# STM32_MPU_IOs.net
KiCad netlist of a schematic drawn in Altium Designer
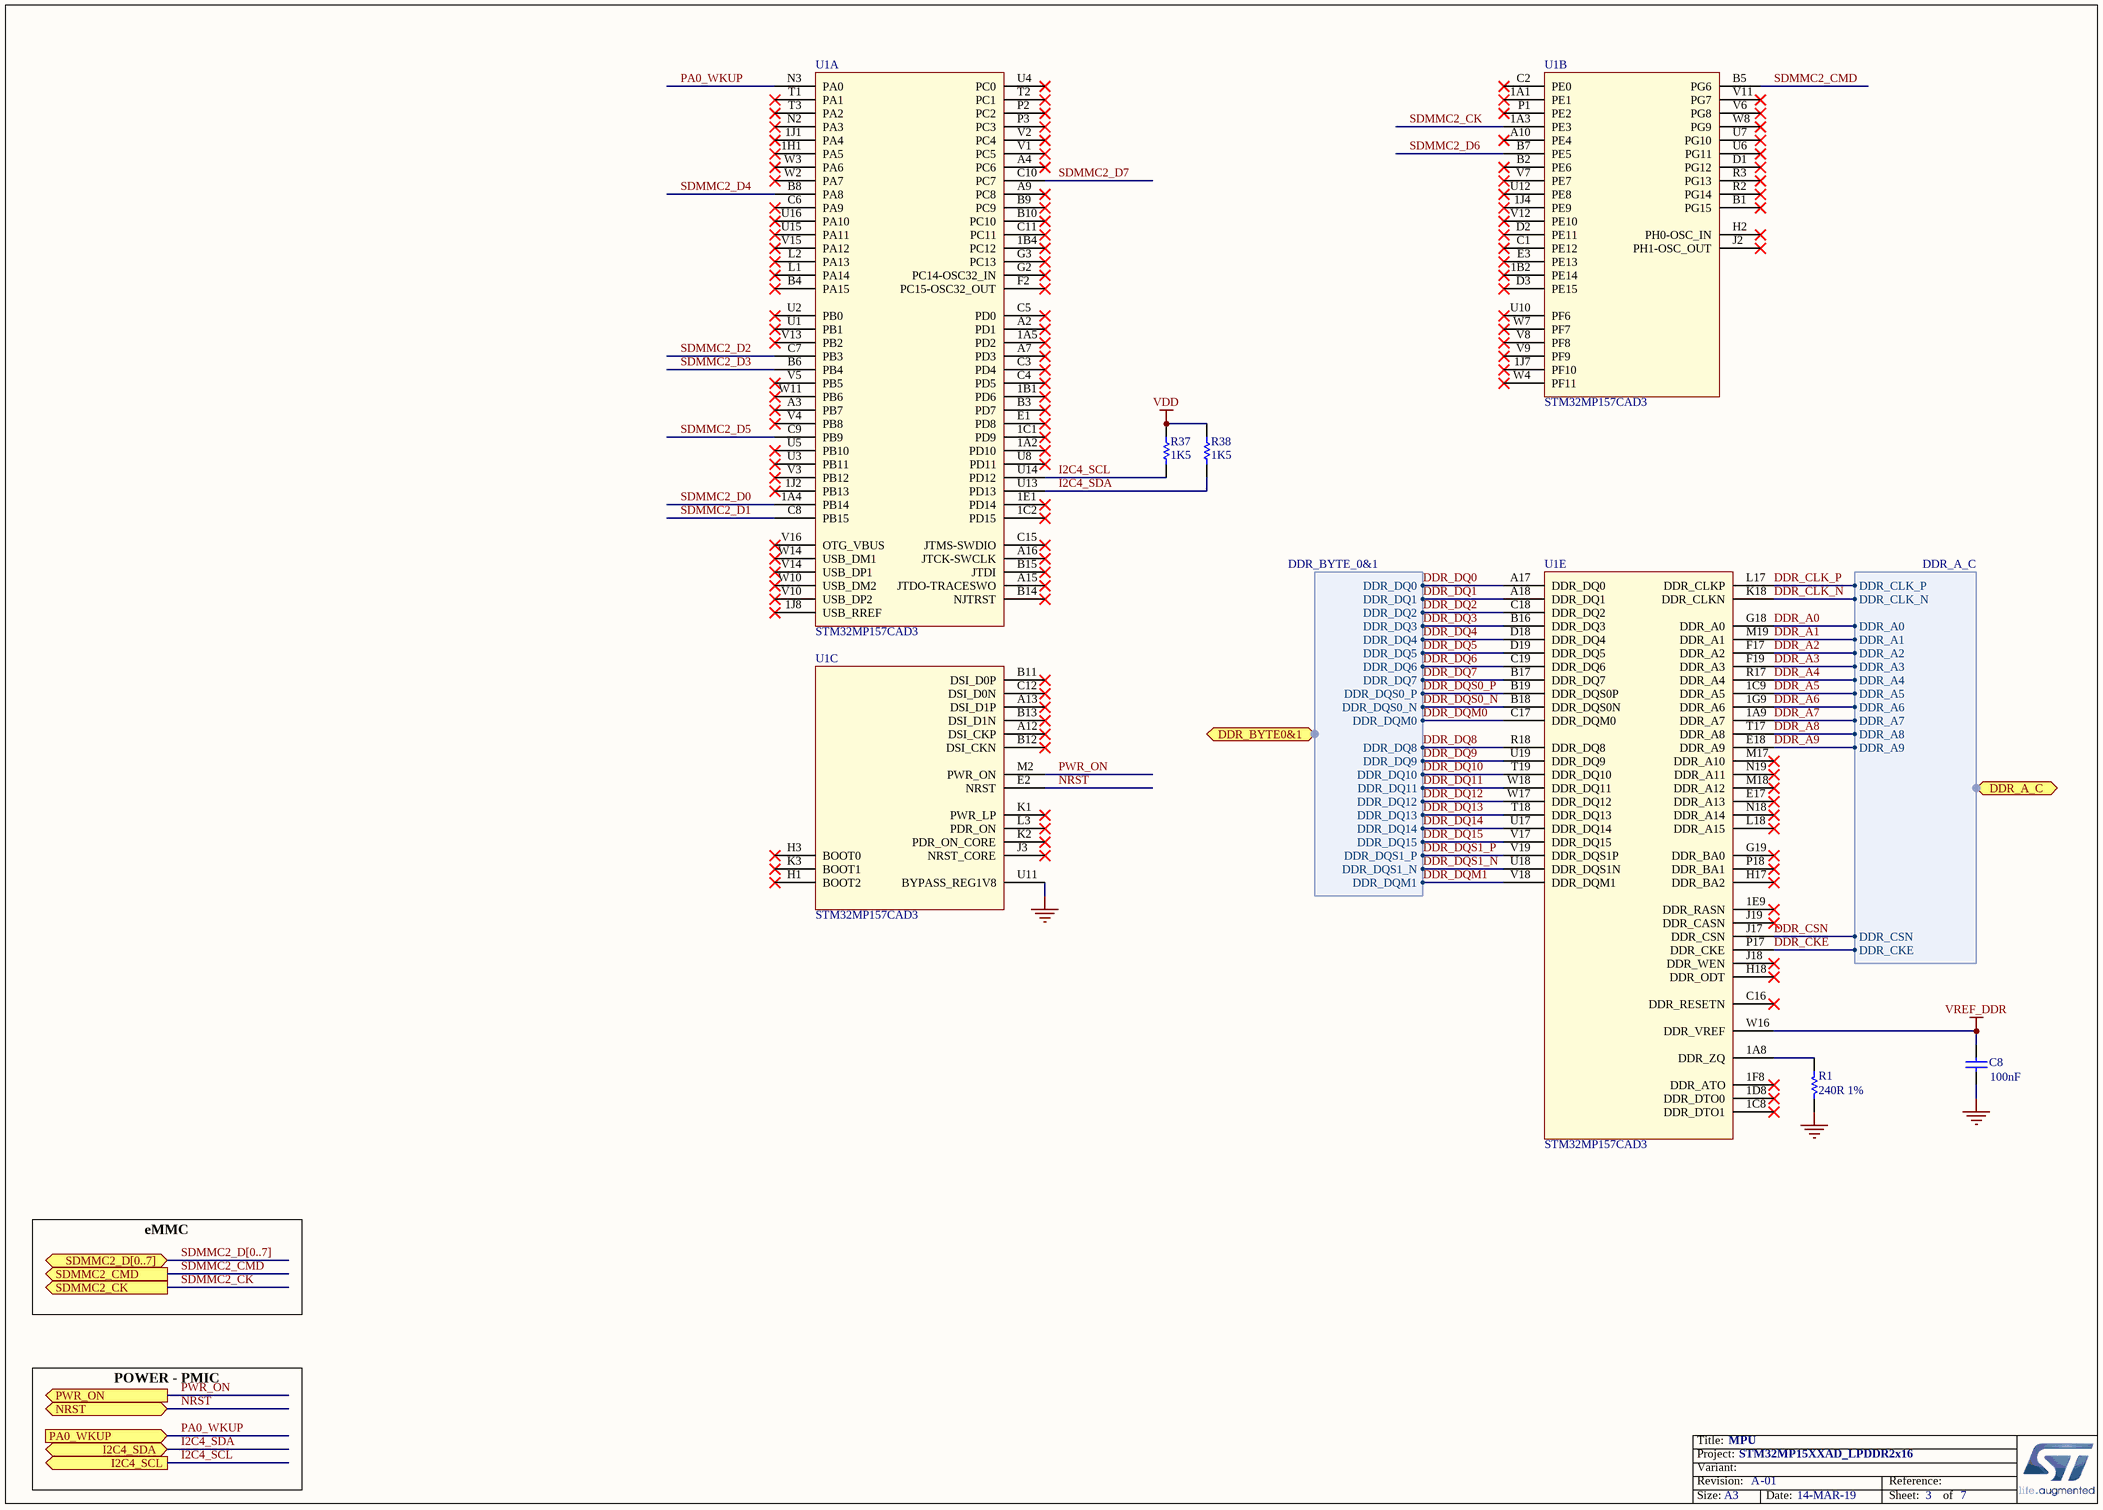
[diagram p0: STM32_MPU_IOs.SchDoc]

(export (version "E")
  (design (tool "Eeschema 10.0.6"))
  (components
    (comp (ref "C8")
      (value "100nF")
      (footprint "C0402")
      (description "Capacitor, MLCC, 100nF, 16V, X7R, 10%, 0402, T=0.5mm")
      (fields
        (field (name "INTERNAL_PART_NUMBER") "MCD-00006")
        (field (name "MANUFACTURER_PART_NUMBER") "CC0402KRX7R7BB104")
        (field (name "PROVIDED_BY") "SUBCO")
      )
      (libsource (lib "MCD_PARTS_database") (part "Capacitor"))
    )
    (comp (ref "R1")
      (value "240R 1%")
      (footprint "R0402")
      (description "Resistor,240R,0402,1%,1/16W")
      (fields
        (field (name "INTERNAL_PART_NUMBER") "MCD-00120")
        (field (name "MANUFACTURER_PART_NUMBER") "RC0402FR-07240RL")
        (field (name "PROVIDED_BY") "SUBCO")
      )
      (libsource (lib "MCD_PARTS_database") (part "Resistor"))
    )
    (comp (ref "R37")
      (value "1K5")
      (footprint "R0402")
      (description "Resistor,1K5,0402,1%,1/16W")
      (fields
        (field (name "INTERNAL_PART_NUMBER") "MCD-00068")
        (field (name "MANUFACTURER_PART_NUMBER") "RC0402FR-071K5L")
        (field (name "PROVIDED_BY") "SUBCO")
      )
      (libsource (lib "MCD_PARTS_database") (part "Resistor"))
    )
    (comp (ref "R38")
      (value "1K5")
      (footprint "R0402")
      (description "Resistor,1K5,0402,1%,1/16W")
      (fields
        (field (name "INTERNAL_PART_NUMBER") "MCD-00068")
        (field (name "MANUFACTURER_PART_NUMBER") "RC0402FR-071K5L")
        (field (name "PROVIDED_BY") "SUBCO")
      )
      (libsource (lib "MCD_PARTS_database") (part "Resistor"))
    )
    (comp (ref "U1")
      (value "STM32MP157CAD3")
      (footprint "ICC_TFBGA257_10X10_STM32MP157CAD3_P050-065")
      (description "MPU TFBGA10x10 secure boot+crypto")
      (fields
        (field (name "INTERNAL_PART_NUMBER") "MCD-01144")
        (field (name "MANUFACTURER") "STMICROELECTRONICS")
        (field (name "PROVIDED_BY") "SUBCO with ST control")
      )
      (libsource (lib "MCD_PARTS_database") (part "STM32MP157CAD3"))
    )
  )
  (nets
    (net (code "3") (name "/DDR_A0") (class "Default")
      (node (ref "U1") (pin "G18") (pinfunction "DDR_A0_G18") (pintype "passive"))
    )
    (net (code "4") (name "/DDR_A1") (class "Default")
      (node (ref "U1") (pin "M19") (pinfunction "DDR_A1_M19") (pintype "passive"))
    )
    (net (code "5") (name "/DDR_A2") (class "Default")
      (node (ref "U1") (pin "F17") (pinfunction "DDR_A2_F17") (pintype "passive"))
    )
    (net (code "6") (name "/DDR_A3") (class "Default")
      (node (ref "U1") (pin "F19") (pinfunction "DDR_A3_F19") (pintype "passive"))
    )
    (net (code "7") (name "/DDR_A4") (class "Default")
      (node (ref "U1") (pin "R17") (pinfunction "DDR_A4_R17") (pintype "passive"))
    )
    (net (code "8") (name "/DDR_A5") (class "Default")
      (node (ref "U1") (pin "1C9") (pinfunction "DDR_A5_1C9") (pintype "passive"))
    )
    (net (code "9") (name "/DDR_A6") (class "Default")
      (node (ref "U1") (pin "1G9") (pinfunction "DDR_A6_1G9") (pintype "passive"))
    )
    (net (code "10") (name "/DDR_A7") (class "Default")
      (node (ref "U1") (pin "1A9") (pinfunction "DDR_A7_1A9") (pintype "passive"))
    )
    (net (code "11") (name "/DDR_A8") (class "Default")
      (node (ref "U1") (pin "T17") (pinfunction "DDR_A8_T17") (pintype "passive"))
    )
    (net (code "12") (name "/DDR_A9") (class "Default")
      (node (ref "U1") (pin "E18") (pinfunction "DDR_A9_E18") (pintype "passive"))
    )
    (net (code "13") (name "/DDR_CKE") (class "Default")
      (node (ref "U1") (pin "P17") (pinfunction "DDR_CKE_P17") (pintype "passive"))
    )
    (net (code "14") (name "/DDR_CLK_N") (class "Default")
      (node (ref "U1") (pin "K18") (pinfunction "DDR_CLKN_K18") (pintype "passive"))
    )
    (net (code "15") (name "/DDR_CLK_P") (class "Default")
      (node (ref "U1") (pin "L17") (pinfunction "DDR_CLKP_L17") (pintype "passive"))
    )
    (net (code "16") (name "/DDR_CSN") (class "Default")
      (node (ref "U1") (pin "J17") (pinfunction "DDR_CSN_J17") (pintype "passive"))
    )
    (net (code "17") (name "/DDR_DQ0") (class "Default")
      (node (ref "U1") (pin "A17") (pinfunction "DDR_DQ0_A17") (pintype "passive"))
    )
    (net (code "18") (name "/DDR_DQ1") (class "Default")
      (node (ref "U1") (pin "A18") (pinfunction "DDR_DQ1_A18") (pintype "passive"))
    )
    (net (code "19") (name "/DDR_DQ2") (class "Default")
      (node (ref "U1") (pin "C18") (pinfunction "DDR_DQ2_C18") (pintype "passive"))
    )
    (net (code "20") (name "/DDR_DQ3") (class "Default")
      (node (ref "U1") (pin "B16") (pinfunction "DDR_DQ3_B16") (pintype "passive"))
    )
    (net (code "21") (name "/DDR_DQ4") (class "Default")
      (node (ref "U1") (pin "D18") (pinfunction "DDR_DQ4_D18") (pintype "passive"))
    )
    (net (code "22") (name "/DDR_DQ5") (class "Default")
      (node (ref "U1") (pin "D19") (pinfunction "DDR_DQ5_D19") (pintype "passive"))
    )
    (net (code "23") (name "/DDR_DQ6") (class "Default")
      (node (ref "U1") (pin "C19") (pinfunction "DDR_DQ6_C19") (pintype "passive"))
    )
    (net (code "24") (name "/DDR_DQ7") (class "Default")
      (node (ref "U1") (pin "B17") (pinfunction "DDR_DQ7_B17") (pintype "passive"))
    )
    (net (code "25") (name "/DDR_DQ8") (class "Default")
      (node (ref "U1") (pin "R18") (pinfunction "DDR_DQ8_R18") (pintype "passive"))
    )
    (net (code "26") (name "/DDR_DQ9") (class "Default")
      (node (ref "U1") (pin "U19") (pinfunction "DDR_DQ9_U19") (pintype "passive"))
    )
    (net (code "27") (name "/DDR_DQ10") (class "Default")
      (node (ref "U1") (pin "T19") (pinfunction "DDR_DQ10_T19") (pintype "passive"))
    )
    (net (code "28") (name "/DDR_DQ11") (class "Default")
      (node (ref "U1") (pin "W18") (pinfunction "DDR_DQ11_W18") (pintype "passive"))
    )
    (net (code "29") (name "/DDR_DQ12") (class "Default")
      (node (ref "U1") (pin "W17") (pinfunction "DDR_DQ12_W17") (pintype "passive"))
    )
    (net (code "30") (name "/DDR_DQ13") (class "Default")
      (node (ref "U1") (pin "T18") (pinfunction "DDR_DQ13_T18") (pintype "passive"))
    )
    (net (code "31") (name "/DDR_DQ14") (class "Default")
      (node (ref "U1") (pin "U17") (pinfunction "DDR_DQ14_U17") (pintype "passive"))
    )
    (net (code "32") (name "/DDR_DQ15") (class "Default")
      (node (ref "U1") (pin "V17") (pinfunction "DDR_DQ15_V17") (pintype "passive"))
    )
    (net (code "33") (name "/DDR_DQM0") (class "Default")
      (node (ref "U1") (pin "C17") (pinfunction "DDR_DQM0_C17") (pintype "passive"))
    )
    (net (code "34") (name "/DDR_DQM1") (class "Default")
      (node (ref "U1") (pin "V18") (pinfunction "DDR_DQM1_V18") (pintype "passive"))
    )
    (net (code "35") (name "/DDR_DQS0_N") (class "Default")
      (node (ref "U1") (pin "B18") (pinfunction "DDR_DQS0N_B18") (pintype "passive"))
    )
    (net (code "36") (name "/DDR_DQS0_P") (class "Default")
      (node (ref "U1") (pin "B19") (pinfunction "DDR_DQS0P_B19") (pintype "passive"))
    )
    (net (code "37") (name "/DDR_DQS1_N") (class "Default")
      (node (ref "U1") (pin "U18") (pinfunction "DDR_DQS1N_U18") (pintype "passive"))
    )
    (net (code "38") (name "/DDR_DQS1_P") (class "Default")
      (node (ref "U1") (pin "V19") (pinfunction "DDR_DQS1P_V19") (pintype "passive"))
    )
    (net (code "39") (name "/I2C4_SCL") (class "Default")
      (node (ref "R37") (pin "2") (pinfunction "2_2") (pintype "passive"))
      (node (ref "U1") (pin "U14") (pinfunction "PD12_U14") (pintype "passive"))
    )
    (net (code "40") (name "/I2C4_SDA") (class "Default")
      (node (ref "R38") (pin "2") (pinfunction "2_2") (pintype "passive"))
      (node (ref "U1") (pin "U13") (pinfunction "PD13_U13") (pintype "passive"))
    )
    (net (code "41") (name "/NRST") (class "Default")
      (node (ref "U1") (pin "E2") (pinfunction "NRST_E2") (pintype "passive"))
    )
    (net (code "42") (name "/PA0_WKUP") (class "Default")
      (node (ref "U1") (pin "N3") (pinfunction "PA0_N3") (pintype "passive"))
    )
    (net (code "43") (name "/PWR_ON") (class "Default")
      (node (ref "U1") (pin "M2") (pinfunction "PWR_ON_M2") (pintype "passive"))
    )
    (net (code "44") (name "/SDMMC2_CK") (class "Default")
      (node (ref "U1") (pin "1A3") (pinfunction "PE3_1A3") (pintype "passive"))
    )
    (net (code "45") (name "/SDMMC2_CMD") (class "Default")
      (node (ref "U1") (pin "B5") (pinfunction "PG6_B5") (pintype "passive"))
    )
    (net (code "46") (name "/SDMMC2_D0") (class "Default")
      (node (ref "U1") (pin "1A4") (pinfunction "PB14_1A4") (pintype "passive"))
    )
    (net (code "47") (name "/SDMMC2_D1") (class "Default")
      (node (ref "U1") (pin "C8") (pinfunction "PB15_C8") (pintype "passive"))
    )
    (net (code "48") (name "/SDMMC2_D2") (class "Default")
      (node (ref "U1") (pin "C7") (pinfunction "PB3_C7") (pintype "passive"))
    )
    (net (code "49") (name "/SDMMC2_D3") (class "Default")
      (node (ref "U1") (pin "B6") (pinfunction "PB4_B6") (pintype "passive"))
    )
    (net (code "50") (name "/SDMMC2_D4") (class "Default")
      (node (ref "U1") (pin "B8") (pinfunction "PA8_B8") (pintype "passive"))
    )
    (net (code "51") (name "/SDMMC2_D5") (class "Default")
      (node (ref "U1") (pin "C9") (pinfunction "PB9_C9") (pintype "passive"))
    )
    (net (code "52") (name "/SDMMC2_D6") (class "Default")
      (node (ref "U1") (pin "B7") (pinfunction "PE5_B7") (pintype "passive"))
    )
    (net (code "53") (name "/SDMMC2_D7") (class "Default")
      (node (ref "U1") (pin "C10") (pinfunction "PC7_C10") (pintype "passive"))
    )
    (net (code "57") (name "GND") (class "Default")
      (node (ref "C8") (pin "1") (pinfunction "1_1") (pintype "passive"))
      (node (ref "R1") (pin "2") (pinfunction "2_2") (pintype "passive"))
      (node (ref "U1") (pin "U11") (pinfunction "BYPASS_REG1V8_U11") (pintype "passive"))
    )
    (net (code "58") (name "Net-(U1E-DDR_ZQ)") (class "Default")
      (node (ref "R1") (pin "1") (pinfunction "1_1") (pintype "passive"))
      (node (ref "U1") (pin "1A8") (pinfunction "DDR_ZQ_1A8") (pintype "passive"))
    )
    (net (code "59") (name "VDD") (class "Default")
      (node (ref "R37") (pin "1") (pinfunction "1_1") (pintype "passive"))
      (node (ref "R38") (pin "1") (pinfunction "1_1") (pintype "passive"))
    )
    (net (code "60") (name "VREF_DDR") (class "Default")
      (node (ref "C8") (pin "2") (pinfunction "2_2") (pintype "passive"))
      (node (ref "U1") (pin "W16") (pinfunction "DDR_VREF_W16") (pintype "passive"))
    )
    (net (code "61") (name "unconnected-(U1A-JTCK-SWCLK-PadA16)") (class "Default")
      (node (ref "U1") (pin "A16") (pinfunction "JTCK-SWCLK_A16") (pintype "passive+no_connect"))
    )
    (net (code "62") (name "unconnected-(U1A-JTDI-PadB15)") (class "Default")
      (node (ref "U1") (pin "B15") (pinfunction "JTDI_B15") (pintype "passive+no_connect"))
    )
    (net (code "63") (name "unconnected-(U1A-JTDO-TRACESWO-PadA15)") (class "Default")
      (node (ref "U1") (pin "A15") (pinfunction "JTDO-TRACESWO_A15") (pintype "passive+no_connect"))
    )
    (net (code "64") (name "unconnected-(U1A-JTMS-SWDIO-PadC15)") (class "Default")
      (node (ref "U1") (pin "C15") (pinfunction "JTMS-SWDIO_C15") (pintype "passive+no_connect"))
    )
    (net (code "65") (name "unconnected-(U1A-NJTRST-PadB14)") (class "Default")
      (node (ref "U1") (pin "B14") (pinfunction "NJTRST_B14") (pintype "passive+no_connect"))
    )
    (net (code "66") (name "unconnected-(U1A-OTG_VBUS-PadV16)") (class "Default")
      (node (ref "U1") (pin "V16") (pinfunction "OTG_VBUS_V16") (pintype "passive+no_connect"))
    )
    (net (code "67") (name "unconnected-(U1A-PA1-PadT1)") (class "Default")
      (node (ref "U1") (pin "T1") (pinfunction "PA1_T1") (pintype "passive+no_connect"))
    )
    (net (code "68") (name "unconnected-(U1A-PA2-PadT3)") (class "Default")
      (node (ref "U1") (pin "T3") (pinfunction "PA2_T3") (pintype "passive+no_connect"))
    )
    (net (code "69") (name "unconnected-(U1A-PA3-PadN2)") (class "Default")
      (node (ref "U1") (pin "N2") (pinfunction "PA3_N2") (pintype "passive+no_connect"))
    )
    (net (code "70") (name "unconnected-(U1A-PA4-Pad1J1)") (class "Default")
      (node (ref "U1") (pin "1J1") (pinfunction "PA4_1J1") (pintype "passive+no_connect"))
    )
    (net (code "71") (name "unconnected-(U1A-PA5-Pad1H1)") (class "Default")
      (node (ref "U1") (pin "1H1") (pinfunction "PA5_1H1") (pintype "passive+no_connect"))
    )
    (net (code "72") (name "unconnected-(U1A-PA6-PadW3)") (class "Default")
      (node (ref "U1") (pin "W3") (pinfunction "PA6_W3") (pintype "passive+no_connect"))
    )
    (net (code "73") (name "unconnected-(U1A-PA7-PadW2)") (class "Default")
      (node (ref "U1") (pin "W2") (pinfunction "PA7_W2") (pintype "passive+no_connect"))
    )
    (net (code "74") (name "unconnected-(U1A-PA9-PadC6)") (class "Default")
      (node (ref "U1") (pin "C6") (pinfunction "PA9_C6") (pintype "passive+no_connect"))
    )
    (net (code "75") (name "unconnected-(U1A-PA10-PadU16)") (class "Default")
      (node (ref "U1") (pin "U16") (pinfunction "PA10_U16") (pintype "passive+no_connect"))
    )
    (net (code "76") (name "unconnected-(U1A-PA11-PadU15)") (class "Default")
      (node (ref "U1") (pin "U15") (pinfunction "PA11_U15") (pintype "passive+no_connect"))
    )
    (net (code "77") (name "unconnected-(U1A-PA12-PadV15)") (class "Default")
      (node (ref "U1") (pin "V15") (pinfunction "PA12_V15") (pintype "passive+no_connect"))
    )
    (net (code "78") (name "unconnected-(U1A-PA13-PadL2)") (class "Default")
      (node (ref "U1") (pin "L2") (pinfunction "PA13_L2") (pintype "passive+no_connect"))
    )
    (net (code "79") (name "unconnected-(U1A-PA14-PadL1)") (class "Default")
      (node (ref "U1") (pin "L1") (pinfunction "PA14_L1") (pintype "passive+no_connect"))
    )
    (net (code "80") (name "unconnected-(U1A-PA15-PadB4)") (class "Default")
      (node (ref "U1") (pin "B4") (pinfunction "PA15_B4") (pintype "passive+no_connect"))
    )
    (net (code "81") (name "unconnected-(U1A-PB0-PadU2)") (class "Default")
      (node (ref "U1") (pin "U2") (pinfunction "PB0_U2") (pintype "passive+no_connect"))
    )
    (net (code "82") (name "unconnected-(U1A-PB1-PadU1)") (class "Default")
      (node (ref "U1") (pin "U1") (pinfunction "PB1_U1") (pintype "passive+no_connect"))
    )
    (net (code "83") (name "unconnected-(U1A-PB2-PadV13)") (class "Default")
      (node (ref "U1") (pin "V13") (pinfunction "PB2_V13") (pintype "passive+no_connect"))
    )
    (net (code "84") (name "unconnected-(U1A-PB5-PadV5)") (class "Default")
      (node (ref "U1") (pin "V5") (pinfunction "PB5_V5") (pintype "passive+no_connect"))
    )
    (net (code "85") (name "unconnected-(U1A-PB6-PadW11)") (class "Default")
      (node (ref "U1") (pin "W11") (pinfunction "PB6_W11") (pintype "passive+no_connect"))
    )
    (net (code "86") (name "unconnected-(U1A-PB7-PadA3)") (class "Default")
      (node (ref "U1") (pin "A3") (pinfunction "PB7_A3") (pintype "passive+no_connect"))
    )
    (net (code "87") (name "unconnected-(U1A-PB8-PadV4)") (class "Default")
      (node (ref "U1") (pin "V4") (pinfunction "PB8_V4") (pintype "passive+no_connect"))
    )
    (net (code "88") (name "unconnected-(U1A-PB10-PadU5)") (class "Default")
      (node (ref "U1") (pin "U5") (pinfunction "PB10_U5") (pintype "passive+no_connect"))
    )
    (net (code "89") (name "unconnected-(U1A-PB11-PadU3)") (class "Default")
      (node (ref "U1") (pin "U3") (pinfunction "PB11_U3") (pintype "passive+no_connect"))
    )
    (net (code "90") (name "unconnected-(U1A-PB12-PadV3)") (class "Default")
      (node (ref "U1") (pin "V3") (pinfunction "PB12_V3") (pintype "passive+no_connect"))
    )
    (net (code "91") (name "unconnected-(U1A-PB13-Pad1J2)") (class "Default")
      (node (ref "U1") (pin "1J2") (pinfunction "PB13_1J2") (pintype "passive+no_connect"))
    )
    (net (code "92") (name "unconnected-(U1A-PC0-PadU4)") (class "Default")
      (node (ref "U1") (pin "U4") (pinfunction "PC0_U4") (pintype "passive+no_connect"))
    )
    (net (code "93") (name "unconnected-(U1A-PC1-PadT2)") (class "Default")
      (node (ref "U1") (pin "T2") (pinfunction "PC1_T2") (pintype "passive+no_connect"))
    )
    (net (code "94") (name "unconnected-(U1A-PC2-PadP2)") (class "Default")
      (node (ref "U1") (pin "P2") (pinfunction "PC2_P2") (pintype "passive+no_connect"))
    )
    (net (code "95") (name "unconnected-(U1A-PC3-PadP3)") (class "Default")
      (node (ref "U1") (pin "P3") (pinfunction "PC3_P3") (pintype "passive+no_connect"))
    )
    (net (code "96") (name "unconnected-(U1A-PC4-PadV2)") (class "Default")
      (node (ref "U1") (pin "V2") (pinfunction "PC4_V2") (pintype "passive+no_connect"))
    )
    (net (code "97") (name "unconnected-(U1A-PC5-PadV1)") (class "Default")
      (node (ref "U1") (pin "V1") (pinfunction "PC5_V1") (pintype "passive+no_connect"))
    )
    (net (code "98") (name "unconnected-(U1A-PC6-PadA4)") (class "Default")
      (node (ref "U1") (pin "A4") (pinfunction "PC6_A4") (pintype "passive+no_connect"))
    )
    (net (code "99") (name "unconnected-(U1A-PC8-PadA9)") (class "Default")
      (node (ref "U1") (pin "A9") (pinfunction "PC8_A9") (pintype "passive+no_connect"))
    )
    (net (code "100") (name "unconnected-(U1A-PC9-PadB9)") (class "Default")
      (node (ref "U1") (pin "B9") (pinfunction "PC9_B9") (pintype "passive+no_connect"))
    )
    (net (code "101") (name "unconnected-(U1A-PC10-PadB10)") (class "Default")
      (node (ref "U1") (pin "B10") (pinfunction "PC10_B10") (pintype "passive+no_connect"))
    )
    (net (code "102") (name "unconnected-(U1A-PC11-PadC11)") (class "Default")
      (node (ref "U1") (pin "C11") (pinfunction "PC11_C11") (pintype "passive+no_connect"))
    )
    (net (code "103") (name "unconnected-(U1A-PC12-Pad1B4)") (class "Default")
      (node (ref "U1") (pin "1B4") (pinfunction "PC12_1B4") (pintype "passive+no_connect"))
    )
    (net (code "104") (name "unconnected-(U1A-PC13-PadG3)") (class "Default")
      (node (ref "U1") (pin "G3") (pinfunction "PC13_G3") (pintype "passive+no_connect"))
    )
    (net (code "105") (name "unconnected-(U1A-PC14-OSC32_IN-PadG2)") (class "Default")
      (node (ref "U1") (pin "G2") (pinfunction "PC14-OSC32_IN_G2") (pintype "passive+no_connect"))
    )
    (net (code "106") (name "unconnected-(U1A-PC15-OSC32_OUT-PadF2)") (class "Default")
      (node (ref "U1") (pin "F2") (pinfunction "PC15-OSC32_OUT_F2") (pintype "passive+no_connect"))
    )
    (net (code "107") (name "unconnected-(U1A-PD0-PadC5)") (class "Default")
      (node (ref "U1") (pin "C5") (pinfunction "PD0_C5") (pintype "passive+no_connect"))
    )
    (net (code "108") (name "unconnected-(U1A-PD1-PadA2)") (class "Default")
      (node (ref "U1") (pin "A2") (pinfunction "PD1_A2") (pintype "passive+no_connect"))
    )
    (net (code "109") (name "unconnected-(U1A-PD2-Pad1A5)") (class "Default")
      (node (ref "U1") (pin "1A5") (pinfunction "PD2_1A5") (pintype "passive+no_connect"))
    )
    (net (code "110") (name "unconnected-(U1A-PD3-PadA7)") (class "Default")
      (node (ref "U1") (pin "A7") (pinfunction "PD3_A7") (pintype "passive+no_connect"))
    )
    (net (code "111") (name "unconnected-(U1A-PD4-PadC3)") (class "Default")
      (node (ref "U1") (pin "C3") (pinfunction "PD4_C3") (pintype "passive+no_connect"))
    )
    (net (code "112") (name "unconnected-(U1A-PD5-PadC4)") (class "Default")
      (node (ref "U1") (pin "C4") (pinfunction "PD5_C4") (pintype "passive+no_connect"))
    )
    (net (code "113") (name "unconnected-(U1A-PD6-Pad1B1)") (class "Default")
      (node (ref "U1") (pin "1B1") (pinfunction "PD6_1B1") (pintype "passive+no_connect"))
    )
    (net (code "114") (name "unconnected-(U1A-PD7-PadB3)") (class "Default")
      (node (ref "U1") (pin "B3") (pinfunction "PD7_B3") (pintype "passive+no_connect"))
    )
    (net (code "115") (name "unconnected-(U1A-PD8-PadE1)") (class "Default")
      (node (ref "U1") (pin "E1") (pinfunction "PD8_E1") (pintype "passive+no_connect"))
    )
    (net (code "116") (name "unconnected-(U1A-PD9-Pad1C1)") (class "Default")
      (node (ref "U1") (pin "1C1") (pinfunction "PD9_1C1") (pintype "passive+no_connect"))
    )
    (net (code "117") (name "unconnected-(U1A-PD10-Pad1A2)") (class "Default")
      (node (ref "U1") (pin "1A2") (pinfunction "PD10_1A2") (pintype "passive+no_connect"))
    )
    (net (code "118") (name "unconnected-(U1A-PD11-PadU8)") (class "Default")
      (node (ref "U1") (pin "U8") (pinfunction "PD11_U8") (pintype "passive+no_connect"))
    )
    (net (code "119") (name "unconnected-(U1A-PD14-Pad1E1)") (class "Default")
      (node (ref "U1") (pin "1E1") (pinfunction "PD14_1E1") (pintype "passive+no_connect"))
    )
    (net (code "120") (name "unconnected-(U1A-PD15-Pad1C2)") (class "Default")
      (node (ref "U1") (pin "1C2") (pinfunction "PD15_1C2") (pintype "passive+no_connect"))
    )
    (net (code "121") (name "unconnected-(U1A-USB_DM1-PadW14)") (class "Default")
      (node (ref "U1") (pin "W14") (pinfunction "USB_DM1_W14") (pintype "passive+no_connect"))
    )
    (net (code "122") (name "unconnected-(U1A-USB_DM2-PadW10)") (class "Default")
      (node (ref "U1") (pin "W10") (pinfunction "USB_DM2_W10") (pintype "passive+no_connect"))
    )
    (net (code "123") (name "unconnected-(U1A-USB_DP1-PadV14)") (class "Default")
      (node (ref "U1") (pin "V14") (pinfunction "USB_DP1_V14") (pintype "passive+no_connect"))
    )
    (net (code "124") (name "unconnected-(U1A-USB_DP2-PadV10)") (class "Default")
      (node (ref "U1") (pin "V10") (pinfunction "USB_DP2_V10") (pintype "passive+no_connect"))
    )
    (net (code "125") (name "unconnected-(U1A-USB_RREF-Pad1J8)") (class "Default")
      (node (ref "U1") (pin "1J8") (pinfunction "USB_RREF_1J8") (pintype "passive+no_connect"))
    )
    (net (code "126") (name "unconnected-(U1B-PE0-PadC2)") (class "Default")
      (node (ref "U1") (pin "C2") (pinfunction "PE0_C2") (pintype "passive+no_connect"))
    )
    (net (code "127") (name "unconnected-(U1B-PE1-Pad1A1)") (class "Default")
      (node (ref "U1") (pin "1A1") (pinfunction "PE1_1A1") (pintype "passive+no_connect"))
    )
    (net (code "128") (name "unconnected-(U1B-PE2-PadP1)") (class "Default")
      (node (ref "U1") (pin "P1") (pinfunction "PE2_P1") (pintype "passive+no_connect"))
    )
    (net (code "129") (name "unconnected-(U1B-PE4-PadA10)") (class "Default")
      (node (ref "U1") (pin "A10") (pinfunction "PE4_A10") (pintype "passive+no_connect"))
    )
    (net (code "130") (name "unconnected-(U1B-PE6-PadB2)") (class "Default")
      (node (ref "U1") (pin "B2") (pinfunction "PE6_B2") (pintype "passive+no_connect"))
    )
    (net (code "131") (name "unconnected-(U1B-PE7-PadV7)") (class "Default")
      (node (ref "U1") (pin "V7") (pinfunction "PE7_V7") (pintype "passive+no_connect"))
    )
    (net (code "132") (name "unconnected-(U1B-PE8-PadU12)") (class "Default")
      (node (ref "U1") (pin "U12") (pinfunction "PE8_U12") (pintype "passive+no_connect"))
    )
    (net (code "133") (name "unconnected-(U1B-PE9-Pad1J4)") (class "Default")
      (node (ref "U1") (pin "1J4") (pinfunction "PE9_1J4") (pintype "passive+no_connect"))
    )
    (net (code "134") (name "unconnected-(U1B-PE10-PadV12)") (class "Default")
      (node (ref "U1") (pin "V12") (pinfunction "PE10_V12") (pintype "passive+no_connect"))
    )
    (net (code "135") (name "unconnected-(U1B-PE11-PadD2)") (class "Default")
      (node (ref "U1") (pin "D2") (pinfunction "PE11_D2") (pintype "passive+no_connect"))
    )
    (net (code "136") (name "unconnected-(U1B-PE12-PadC1)") (class "Default")
      (node (ref "U1") (pin "C1") (pinfunction "PE12_C1") (pintype "passive+no_connect"))
    )
    (net (code "137") (name "unconnected-(U1B-PE13-PadE3)") (class "Default")
      (node (ref "U1") (pin "E3") (pinfunction "PE13_E3") (pintype "passive+no_connect"))
    )
    (net (code "138") (name "unconnected-(U1B-PE14-Pad1B2)") (class "Default")
      (node (ref "U1") (pin "1B2") (pinfunction "PE14_1B2") (pintype "passive+no_connect"))
    )
    (net (code "139") (name "unconnected-(U1B-PE15-PadD3)") (class "Default")
      (node (ref "U1") (pin "D3") (pinfunction "PE15_D3") (pintype "passive+no_connect"))
    )
    (net (code "140") (name "unconnected-(U1B-PF6-PadU10)") (class "Default")
      (node (ref "U1") (pin "U10") (pinfunction "PF6_U10") (pintype "passive+no_connect"))
    )
    (net (code "141") (name "unconnected-(U1B-PF7-PadW7)") (class "Default")
      (node (ref "U1") (pin "W7") (pinfunction "PF7_W7") (pintype "passive+no_connect"))
    )
    (net (code "142") (name "unconnected-(U1B-PF8-PadV8)") (class "Default")
      (node (ref "U1") (pin "V8") (pinfunction "PF8_V8") (pintype "passive+no_connect"))
    )
    (net (code "143") (name "unconnected-(U1B-PF9-PadV9)") (class "Default")
      (node (ref "U1") (pin "V9") (pinfunction "PF9_V9") (pintype "passive+no_connect"))
    )
    (net (code "144") (name "unconnected-(U1B-PF10-Pad1J7)") (class "Default")
      (node (ref "U1") (pin "1J7") (pinfunction "PF10_1J7") (pintype "passive+no_connect"))
    )
    (net (code "145") (name "unconnected-(U1B-PF11-PadW4)") (class "Default")
      (node (ref "U1") (pin "W4") (pinfunction "PF11_W4") (pintype "passive+no_connect"))
    )
    (net (code "146") (name "unconnected-(U1B-PG7-PadV11)") (class "Default")
      (node (ref "U1") (pin "V11") (pinfunction "PG7_V11") (pintype "passive+no_connect"))
    )
    (net (code "147") (name "unconnected-(U1B-PG8-PadV6)") (class "Default")
      (node (ref "U1") (pin "V6") (pinfunction "PG8_V6") (pintype "passive+no_connect"))
    )
    (net (code "148") (name "unconnected-(U1B-PG9-PadW8)") (class "Default")
      (node (ref "U1") (pin "W8") (pinfunction "PG9_W8") (pintype "passive+no_connect"))
    )
    (net (code "149") (name "unconnected-(U1B-PG10-PadU7)") (class "Default")
      (node (ref "U1") (pin "U7") (pinfunction "PG10_U7") (pintype "passive+no_connect"))
    )
    (net (code "150") (name "unconnected-(U1B-PG11-PadU6)") (class "Default")
      (node (ref "U1") (pin "U6") (pinfunction "PG11_U6") (pintype "passive+no_connect"))
    )
    (net (code "151") (name "unconnected-(U1B-PG12-PadD1)") (class "Default")
      (node (ref "U1") (pin "D1") (pinfunction "PG12_D1") (pintype "passive+no_connect"))
    )
    (net (code "152") (name "unconnected-(U1B-PG13-PadR3)") (class "Default")
      (node (ref "U1") (pin "R3") (pinfunction "PG13_R3") (pintype "passive+no_connect"))
    )
    (net (code "153") (name "unconnected-(U1B-PG14-PadR2)") (class "Default")
      (node (ref "U1") (pin "R2") (pinfunction "PG14_R2") (pintype "passive+no_connect"))
    )
    (net (code "154") (name "unconnected-(U1B-PG15-PadB1)") (class "Default")
      (node (ref "U1") (pin "B1") (pinfunction "PG15_B1") (pintype "passive+no_connect"))
    )
    (net (code "155") (name "unconnected-(U1B-PH0-OSC_IN-PadH2)") (class "Default")
      (node (ref "U1") (pin "H2") (pinfunction "PH0-OSC_IN_H2") (pintype "passive+no_connect"))
    )
    (net (code "156") (name "unconnected-(U1B-PH1-OSC_OUT-PadJ2)") (class "Default")
      (node (ref "U1") (pin "J2") (pinfunction "PH1-OSC_OUT_J2") (pintype "passive+no_connect"))
    )
    (net (code "157") (name "unconnected-(U1C-BOOT0-PadH3)") (class "Default")
      (node (ref "U1") (pin "H3") (pinfunction "BOOT0_H3") (pintype "passive+no_connect"))
    )
    (net (code "158") (name "unconnected-(U1C-BOOT1-PadK3)") (class "Default")
      (node (ref "U1") (pin "K3") (pinfunction "BOOT1_K3") (pintype "passive+no_connect"))
    )
    (net (code "159") (name "unconnected-(U1C-BOOT2-PadH1)") (class "Default")
      (node (ref "U1") (pin "H1") (pinfunction "BOOT2_H1") (pintype "passive+no_connect"))
    )
    (net (code "160") (name "unconnected-(U1C-DSI_CKN-PadB12)") (class "Default")
      (node (ref "U1") (pin "B12") (pinfunction "DSI_CKN_B12") (pintype "passive+no_connect"))
    )
    (net (code "161") (name "unconnected-(U1C-DSI_CKP-PadA12)") (class "Default")
      (node (ref "U1") (pin "A12") (pinfunction "DSI_CKP_A12") (pintype "passive+no_connect"))
    )
    (net (code "162") (name "unconnected-(U1C-DSI_D0N-PadC12)") (class "Default")
      (node (ref "U1") (pin "C12") (pinfunction "DSI_D0N_C12") (pintype "passive+no_connect"))
    )
    (net (code "163") (name "unconnected-(U1C-DSI_D0P-PadB11)") (class "Default")
      (node (ref "U1") (pin "B11") (pinfunction "DSI_D0P_B11") (pintype "passive+no_connect"))
    )
    (net (code "164") (name "unconnected-(U1C-DSI_D1N-PadB13)") (class "Default")
      (node (ref "U1") (pin "B13") (pinfunction "DSI_D1N_B13") (pintype "passive+no_connect"))
    )
    (net (code "165") (name "unconnected-(U1C-DSI_D1P-PadA13)") (class "Default")
      (node (ref "U1") (pin "A13") (pinfunction "DSI_D1P_A13") (pintype "passive+no_connect"))
    )
    (net (code "166") (name "unconnected-(U1C-NRST_CORE-PadJ3)") (class "Default")
      (node (ref "U1") (pin "J3") (pinfunction "NRST_CORE_J3") (pintype "passive+no_connect"))
    )
    (net (code "167") (name "unconnected-(U1C-PDR_ON-PadL3)") (class "Default")
      (node (ref "U1") (pin "L3") (pinfunction "PDR_ON_L3") (pintype "passive+no_connect"))
    )
    (net (code "168") (name "unconnected-(U1C-PDR_ON_CORE-PadK2)") (class "Default")
      (node (ref "U1") (pin "K2") (pinfunction "PDR_ON_CORE_K2") (pintype "passive+no_connect"))
    )
    (net (code "169") (name "unconnected-(U1C-PWR_LP-PadK1)") (class "Default")
      (node (ref "U1") (pin "K1") (pinfunction "PWR_LP_K1") (pintype "passive+no_connect"))
    )
    (net (code "170") (name "unconnected-(U1E-DDR_A10-PadM17)") (class "Default")
      (node (ref "U1") (pin "M17") (pinfunction "DDR_A10_M17") (pintype "passive+no_connect"))
    )
    (net (code "171") (name "unconnected-(U1E-DDR_A11-PadN19)") (class "Default")
      (node (ref "U1") (pin "N19") (pinfunction "DDR_A11_N19") (pintype "passive+no_connect"))
    )
    (net (code "172") (name "unconnected-(U1E-DDR_A12-PadM18)") (class "Default")
      (node (ref "U1") (pin "M18") (pinfunction "DDR_A12_M18") (pintype "passive+no_connect"))
    )
    (net (code "173") (name "unconnected-(U1E-DDR_A13-PadE17)") (class "Default")
      (node (ref "U1") (pin "E17") (pinfunction "DDR_A13_E17") (pintype "passive+no_connect"))
    )
    (net (code "174") (name "unconnected-(U1E-DDR_A14-PadN18)") (class "Default")
      (node (ref "U1") (pin "N18") (pinfunction "DDR_A14_N18") (pintype "passive+no_connect"))
    )
    (net (code "175") (name "unconnected-(U1E-DDR_A15-PadL18)") (class "Default")
      (node (ref "U1") (pin "L18") (pinfunction "DDR_A15_L18") (pintype "passive+no_connect"))
    )
    (net (code "176") (name "unconnected-(U1E-DDR_ATO-Pad1F8)") (class "Default")
      (node (ref "U1") (pin "1F8") (pinfunction "DDR_ATO_1F8") (pintype "passive+no_connect"))
    )
    (net (code "177") (name "unconnected-(U1E-DDR_BA0-PadG19)") (class "Default")
      (node (ref "U1") (pin "G19") (pinfunction "DDR_BA0_G19") (pintype "passive+no_connect"))
    )
    (net (code "178") (name "unconnected-(U1E-DDR_BA1-PadP18)") (class "Default")
      (node (ref "U1") (pin "P18") (pinfunction "DDR_BA1_P18") (pintype "passive+no_connect"))
    )
    (net (code "179") (name "unconnected-(U1E-DDR_BA2-PadH17)") (class "Default")
      (node (ref "U1") (pin "H17") (pinfunction "DDR_BA2_H17") (pintype "passive+no_connect"))
    )
    (net (code "180") (name "unconnected-(U1E-DDR_CASN-PadJ19)") (class "Default")
      (node (ref "U1") (pin "J19") (pinfunction "DDR_CASN_J19") (pintype "passive+no_connect"))
    )
    (net (code "181") (name "unconnected-(U1E-DDR_DTO0-Pad1D8)") (class "Default")
      (node (ref "U1") (pin "1D8") (pinfunction "DDR_DTO0_1D8") (pintype "passive+no_connect"))
    )
    (net (code "182") (name "unconnected-(U1E-DDR_DTO1-Pad1C8)") (class "Default")
      (node (ref "U1") (pin "1C8") (pinfunction "DDR_DTO1_1C8") (pintype "passive+no_connect"))
    )
    (net (code "183") (name "unconnected-(U1E-DDR_ODT-PadH18)") (class "Default")
      (node (ref "U1") (pin "H18") (pinfunction "DDR_ODT_H18") (pintype "passive+no_connect"))
    )
    (net (code "184") (name "unconnected-(U1E-DDR_RASN-Pad1E9)") (class "Default")
      (node (ref "U1") (pin "1E9") (pinfunction "DDR_RASN_1E9") (pintype "passive+no_connect"))
    )
    (net (code "185") (name "unconnected-(U1E-DDR_RESETN-PadC16)") (class "Default")
      (node (ref "U1") (pin "C16") (pinfunction "DDR_RESETN_C16") (pintype "passive+no_connect"))
    )
    (net (code "186") (name "unconnected-(U1E-DDR_WEN-PadJ18)") (class "Default")
      (node (ref "U1") (pin "J18") (pinfunction "DDR_WEN_J18") (pintype "passive+no_connect"))
    )
  )
)
